# Sheet1.net
KiCad netlist of a schematic drawn in Altium Designer
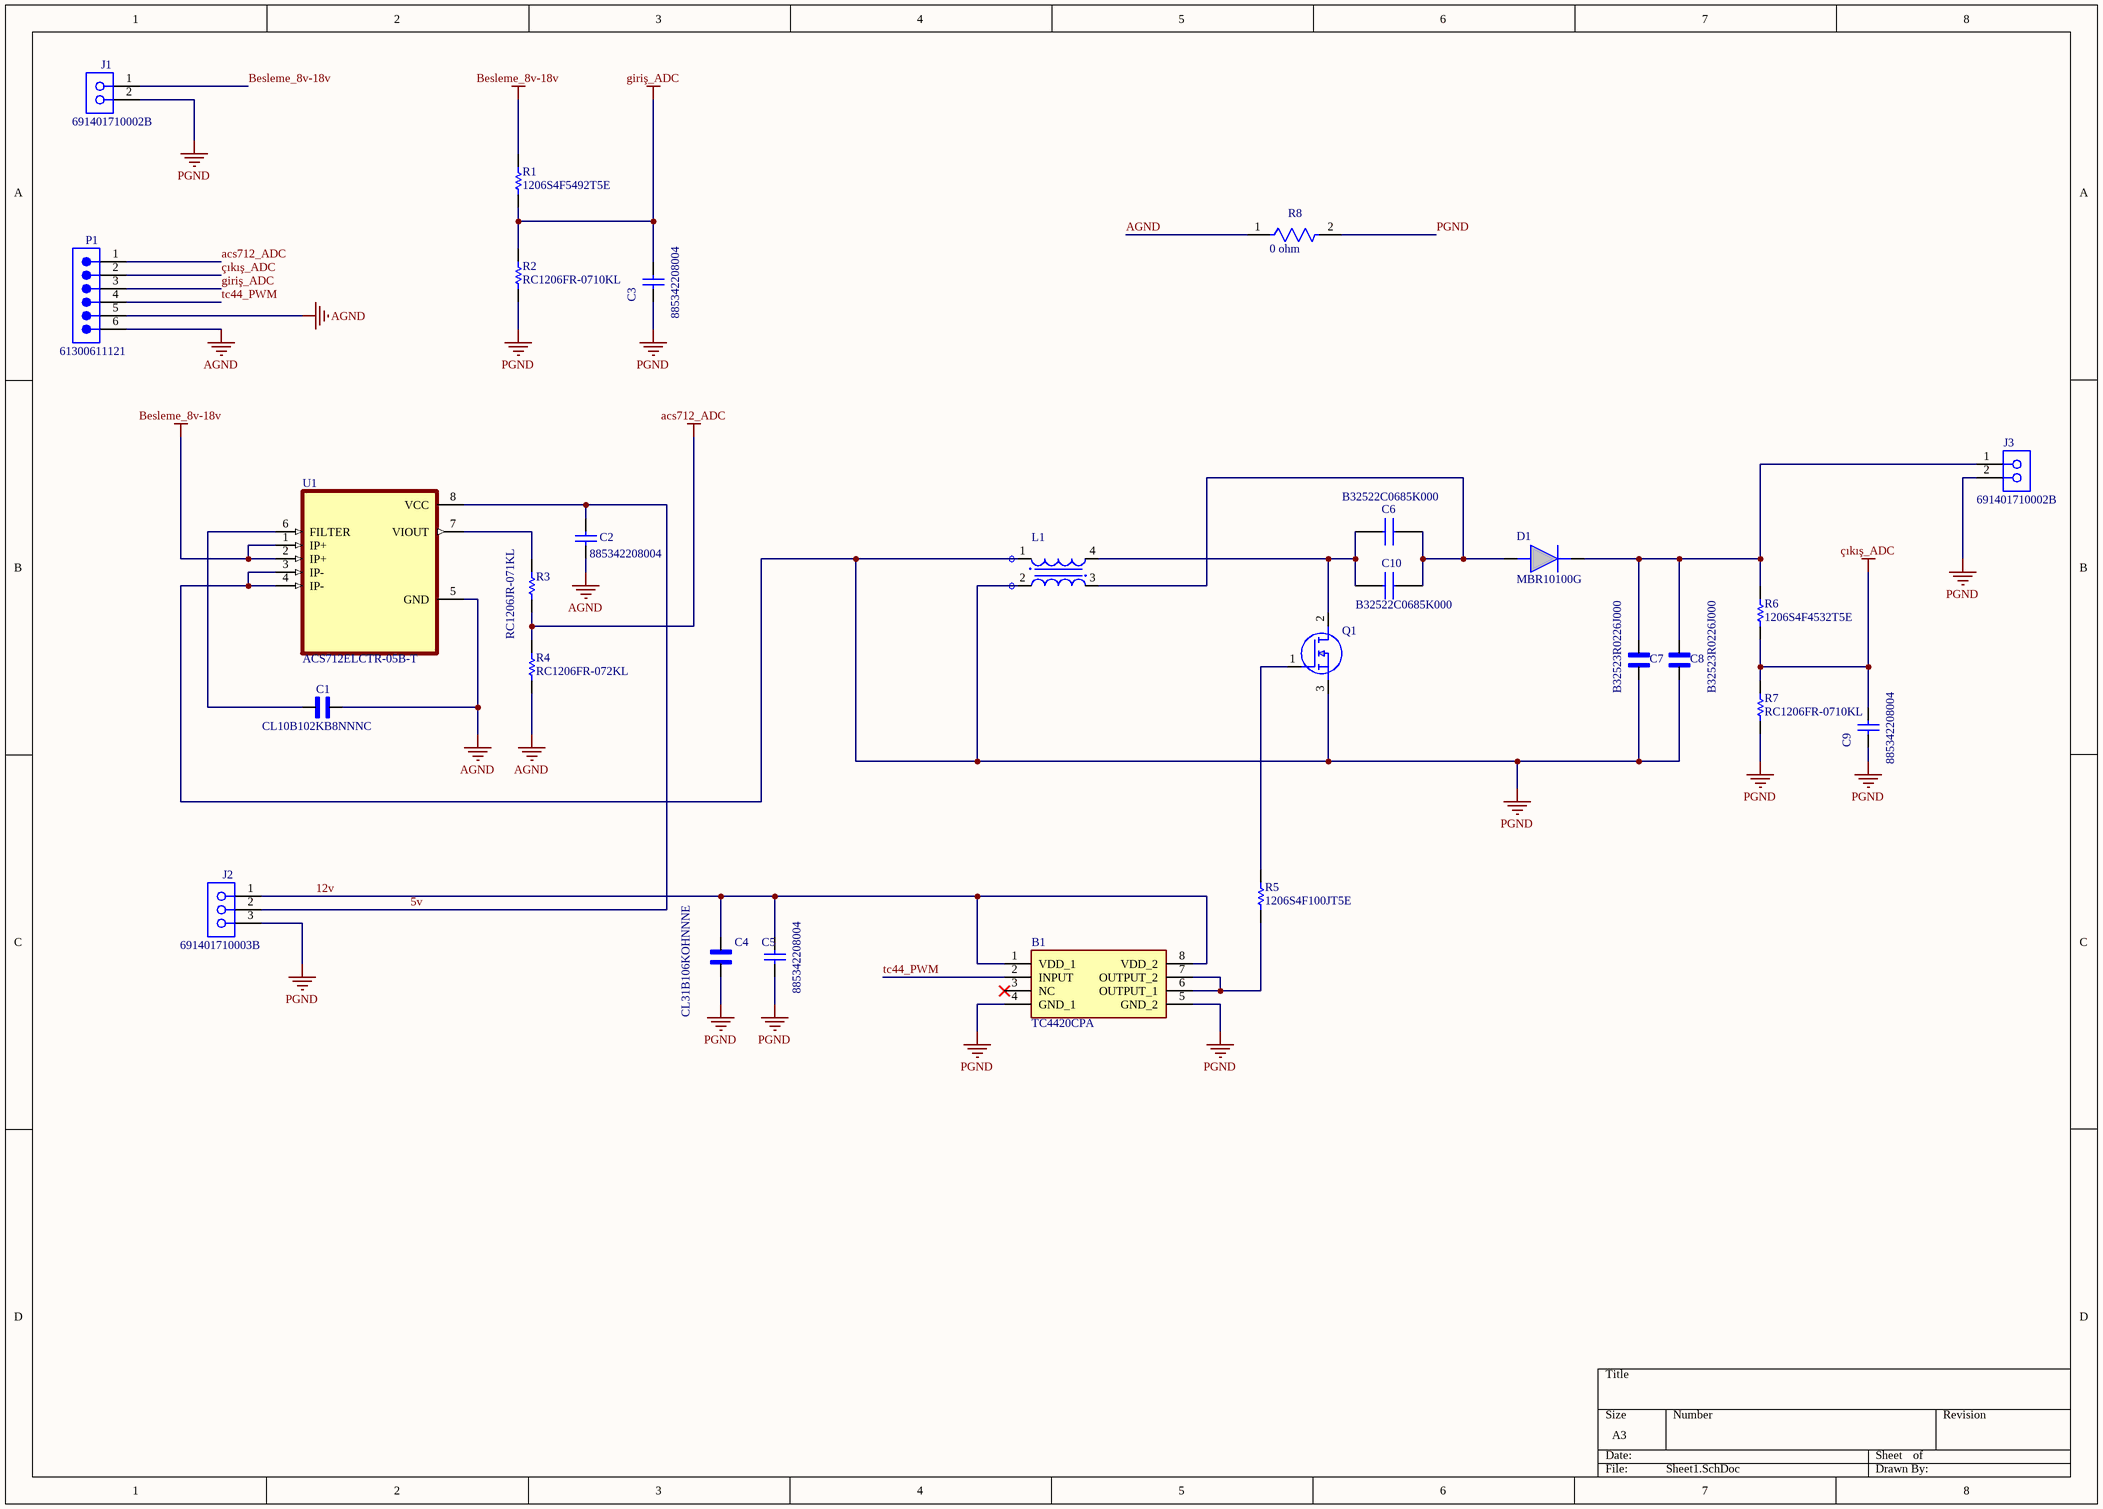
[diagram p0: Sheet1.SchDoc]

(export (version "E")
  (design (tool "Eeschema 10.0.6"))
  (components
    (comp (ref "B1")
      (value "TC4420CPA")
      (footprint "DIP794W56P254L946H432Q8N")
      (description "Microchip TC4420CPA, MOSFET Power Driver 6A, 4.5  18 V, Non-Inverting, 8-Pin PDIP")
      (fields (field (name "MOUSER PART NUMBER") "579-TC4420CPA"))
      (libsource (lib "bitirme_2209_Library2") (part "TC4420CPA"))
    )
    (comp (ref "C1")
      (value "CL10B102KB8NNNC")
      (footprint "CAPC1608X90N")
      (fields (field (name "MF") "{'manufacturer': u'Samsung Electro-Mechanics'}"))
      (libsource (lib "bitirme_2209_Library2") (part "CL10B102KB8NNNC"))
    )
    (comp (ref "C2")
      (value "885342208004")
      (footprint "WCAP-CSMH_1206_H1.6")
      (description "0.1μF ±10% 250V Ceramic Capacitor X7R 1206 (3216 Metric)")
      (libsource (lib "Library2_bitirme_yeni") (part "CMP-03913-89205750-2"))
    )
    (comp (ref "C3")
      (value "885342208004")
      (footprint "WCAP-CSMH_1206_H1.6")
      (description "0.1μF ±10% 250V Ceramic Capacitor X7R 1206 (3216 Metric)")
      (libsource (lib "bitirme_2209_Library2") (part "CMP-03913-89205750-2"))
    )
    (comp (ref "C4")
      (value "CL31B106KOHNNNE")
      (footprint "CAPC3216X180N")
      (description "10 ÂµF Â±10% 16V Ceramic Capacitor X7R 1206 (3216 Metric)")
      (fields (field (name "MF") "Samsung"))
      (libsource (lib "bitirme_2209_Library2") (part "CL31B106KOHNNNE"))
    )
    (comp (ref "C5")
      (value "885342208004")
      (footprint "WCAP-CSMH_1206_H1.6")
      (description "0.1μF ±10% 250V Ceramic Capacitor X7R 1206 (3216 Metric)")
      (libsource (lib "bitirme_2209_Library2") (part "CMP-03913-89205750-2"))
    )
    (comp (ref "C6")
      (value "B32522C0685K000")
      (footprint "B32522C0685K000")
      (description "Metallized Polyester Capacitors (MKT), 6.8uF, 63V DC, 8.5mm(W) x 14.5mm(H) x 18mm(L)")
      (fields (field (name "MOUSER PART NUMBER") "871-B32522C685K"))
      (libsource (lib "bitirme_2209_Library2") (part "B32522C0685K000"))
    )
    (comp (ref "C7")
      (value "B32523R0226J000")
      (footprint "CAPRR2250W80L2650T1200H2200")
      (fields (field (name "MF") "TDK"))
      (libsource (lib "bitirme_2209_Library2") (part "B32523R0226J000"))
    )
    (comp (ref "C8")
      (value "B32523R0226J000")
      (footprint "CAPRR2250W80L2650T1200H2200")
      (fields (field (name "MF") "TDK"))
      (libsource (lib "bitirme_2209_Library2") (part "B32523R0226J000"))
    )
    (comp (ref "C9")
      (value "885342208004")
      (footprint "WCAP-CSMH_1206_H1.6")
      (description "0.1μF ±10% 250V Ceramic Capacitor X7R 1206 (3216 Metric)")
      (libsource (lib "bitirme_2209_Library2") (part "CMP-03913-89205750-2"))
    )
    (comp (ref "C10")
      (value "B32522C0685K000")
      (footprint "B32522C0685K000")
      (description "Metallized Polyester Capacitors (MKT), 6.8uF, 63V DC, 8.5mm(W) x 14.5mm(H) x 18mm(L)")
      (fields (field (name "MOUSER PART NUMBER") "871-B32522C685K"))
      (libsource (lib "bitirme_2209_Library2") (part "B32522C0685K000"))
    )
    (comp (ref "D1")
      (value "MBR10100G")
      (footprint "TO508P997X444X1905-2")
      (fields (field (name "MOUSER PART NUMBER") "863-MBR10100G"))
      (libsource (lib "bitirme_2209_Library2") (part "MBR10100G"))
    )
    (comp (ref "J1")
      (value "691401710002B")
      (footprint "691401710002B")
      (description "Terminal Block, 5.00MM Screwless Horizontal, 2.0MM 2 Wires, 14-24 AWG, 2 Pin")
      (libsource (lib "bitirme_2209_Library2") (part "CMP-1502-03003-3"))
    )
    (comp (ref "J2")
      (value "691401710003B")
      (footprint "691401710003B")
      (description "Terminal Block, 5.00MM Screwless Horizontal, 2.0MM 2 Wires, 14-24 AWG, 3 Pin")
      (libsource (lib "bitirme_2209_Library2") (part "CMP-1502-03004-3"))
    )
    (comp (ref "J3")
      (value "691401710002B")
      (footprint "691401710002B")
      (description "Terminal Block, 5.00MM Screwless Horizontal, 2.0MM 2 Wires, 14-24 AWG, 2 Pin")
      (libsource (lib "bitirme_2209_Library2") (part "CMP-1502-03003-3"))
    )
    (comp (ref "L1")
      (value "WE-CFWI_1312")
      (footprint "caupled ınductor")
      (fields
        (field (name "MF") "{'manufacturer': u'~{W}xfcrth Elektronik'}")
        (field (name "MP") "74485540101")
      )
      (libsource (lib "Library2_bitirme_yeni") (part "WE-CFWI_1312"))
    )
    (comp (ref "P1")
      (value "61300611121")
      (footprint "61300611121")
      (description "THT Vertical Pin Header WR-PHD, Pitch 2.54 mm, Single Row, 6 pins")
      (libsource (lib "bitirme_2209_Library2") (part "CMP-1502-01070-4"))
    )
    (comp (ref "Q1")
      (value "IXTP110N055T2 hortizol")
      (footprint "TO254P1054X470X1955-3")
      (fields
        (field (name "MF") "{'manufacturer': u'Texas Instruments'}")
        (field (name "MP") "LM7805CT/NOPB")
      )
      (libsource (lib "bitirme_2209_Library2") (part "LM7805CT/NOPB"))
    )
    (comp (ref "R1")
      (value "1206S4F5492T5E")
      (footprint "RESC3116X65X40ML10T20")
      (description "Chip Resistor, 10 KOhm, +/- 1%, 0.25 W, -55 to 155 degC, 1206 (3216 Metric), RoHS, Tape and Reel")
      (fields (field (name "TOLERANCE") "1%") (field (name "MANUFACTURER") "Yageo"))
      (libsource (lib "bitirme_2209_Library2") (part "RC1206FR-0710KL"))
    )
    (comp (ref "R2")
      (value "RC1206FR-0710KL")
      (footprint "RESC3116X65X40ML10T20")
      (description "Chip Resistor, 10 KOhm, +/- 1%, 0.25 W, -55 to 155 degC, 1206 (3216 Metric), RoHS, Tape and Reel")
      (fields (field (name "TOLERANCE") "1%") (field (name "MANUFACTURER") "Yageo"))
      (libsource (lib "bitirme_2209_Library2") (part "RC1206FR-0710KL"))
    )
    (comp (ref "R3")
      (value "RC1206JR-071KL")
      (footprint "RESC3116X65X40ML10T20")
      (description "Chip Resistor, 10 KOhm, +/- 1%, 0.25 W, -55 to 155 degC, 1206 (3216 Metric), RoHS, Tape and Reel")
      (fields (field (name "TOLERANCE") "1%") (field (name "MANUFACTURER") "Yageo"))
      (libsource (lib "bitirme_2209_Library2") (part "RC1206FR-0710KL"))
    )
    (comp (ref "R4")
      (value "RC1206FR-072KL")
      (footprint "RESC3116X65X40ML10T20")
      (fields (field (name "MANUFACTURER") "Yageo") (field (name "PART NUMBER") "RC1206FR-101K21L"))
      (libsource (lib "bitirme_2209_Library2") (part "RC1206FR-072KL"))
    )
    (comp (ref "R5")
      (value "1206S4F100JT5E")
      (footprint "RESC3116X65X40ML10T20")
      (description "Chip Resistor, 10 KOhm, +/- 1%, 0.25 W, -55 to 155 degC, 1206 (3216 Metric), RoHS, Tape and Reel")
      (fields (field (name "TOLERANCE") "1%") (field (name "MANUFACTURER") "Yageo"))
      (libsource (lib "bitirme_2209_Library2") (part "RC1206FR-0736KL"))
    )
    (comp (ref "R6")
      (value "1206S4F4532T5E")
      (footprint "RESC3116X65X40ML10T20")
      (description "Chip Resistor, 10 KOhm, +/- 1%, 0.25 W, -55 to 155 degC, 1206 (3216 Metric), RoHS, Tape and Reel")
      (fields (field (name "TOLERANCE") "1%") (field (name "MANUFACTURER") "Yageo"))
      (libsource (lib "bitirme_2209_Library2") (part "RC1206FR-0710KL"))
    )
    (comp (ref "R7")
      (value "RC1206FR-0710KL")
      (footprint "RESC3116X65X40ML10T20")
      (description "Chip Resistor, 10 KOhm, +/- 1%, 0.25 W, -55 to 155 degC, 1206 (3216 Metric), RoHS, Tape and Reel")
      (fields (field (name "TOLERANCE") "1%") (field (name "MANUFACTURER") "Yageo"))
      (libsource (lib "bitirme_2209_Library2") (part "RC1206FR-0710KL"))
    )
    (comp (ref "R8")
      (value "0 ohm")
      (footprint "FP-RT0805-MFG")
      (description "RES SMD 681 OHM 0.1% 1/8W 0805")
      (fields
        (field (name "MANUFACTURER") "Yageo")
        (field (name "MANUFACTURER PART NUMBER") "RT0805BRD07681RL")
      )
      (libsource (lib "bitirme_2209_Library2") (part "0 ohm"))
    )
    (comp (ref "U1")
      (value "ACS712ELCTR-05B-T")
      (footprint "SOIC127P600X175-8N")
      (fields (field (name "MF") "{'manufacturer': u'Allegro MicroSystems'}"))
      (libsource (lib "bitirme_2209_Library2") (part "ACS712ELCTR-05B-T"))
    )
  )
  (nets
    (net (code "1") (name "/5v") (class "Default")
      (node (ref "C2") (pin "2") (pinfunction "2_2") (pintype "passive"))
      (node (ref "J2") (pin "2") (pinfunction "2_2") (pintype "passive"))
      (node (ref "U1") (pin "8") (pinfunction "VCC_8") (pintype "power_in"))
    )
    (net (code "2") (name "/12v") (class "Default")
      (node (ref "B1") (pin "1") (pinfunction "VDD_1_1") (pintype "passive"))
      (node (ref "B1") (pin "8") (pinfunction "VDD_2_8") (pintype "passive"))
      (node (ref "C4") (pin "2") (pinfunction "2_2") (pintype "passive"))
      (node (ref "C5") (pin "2") (pinfunction "2_2") (pintype "passive"))
      (node (ref "J2") (pin "1") (pinfunction "1_1") (pintype "passive"))
    )
    (net (code "3") (name "/tc44_PWM") (class "Default")
      (node (ref "B1") (pin "2") (pinfunction "INPUT_2") (pintype "passive"))
      (node (ref "P1") (pin "4") (pinfunction "4_4") (pintype "passive"))
    )
    (net (code "4") (name "AGND") (class "Default")
      (node (ref "C1") (pin "2") (pinfunction "2_2") (pintype "passive"))
      (node (ref "C2") (pin "1") (pinfunction "1_1") (pintype "passive"))
      (node (ref "P1") (pin "5") (pinfunction "5_5") (pintype "passive"))
      (node (ref "P1") (pin "6") (pinfunction "6_6") (pintype "passive"))
      (node (ref "R4") (pin "1") (pinfunction "1_1") (pintype "passive"))
      (node (ref "R8") (pin "1") (pinfunction "1_1") (pintype "passive"))
      (node (ref "U1") (pin "5") (pinfunction "GND_5") (pintype "power_in"))
    )
    (net (code "5") (name "Besleme_8v-18v") (class "Default")
      (node (ref "J1") (pin "1") (pinfunction "1_1") (pintype "passive"))
      (node (ref "R1") (pin "2") (pinfunction "2_2") (pintype "passive"))
      (node (ref "U1") (pin "1") (pinfunction "IP+_1") (pintype "input"))
      (node (ref "U1") (pin "2") (pinfunction "IP+_2") (pintype "input"))
    )
    (net (code "6") (name "Net-(B1-OUTPUT_1)") (class "Default")
      (node (ref "B1") (pin "6") (pinfunction "OUTPUT_1_6") (pintype "passive"))
      (node (ref "B1") (pin "7") (pinfunction "OUTPUT_2_7") (pintype "passive"))
      (node (ref "R5") (pin "1") (pinfunction "1_1") (pintype "passive"))
    )
    (net (code "7") (name "Net-(D1-A)") (class "Default")
      (node (ref "C10") (pin "2") (pinfunction "2_2") (pintype "passive"))
      (node (ref "C6") (pin "2") (pinfunction "2_2") (pintype "passive"))
      (node (ref "D1") (pin "3") (pinfunction "A_3") (pintype "passive"))
      (node (ref "L1") (pin "3") (pinfunction "3_3") (pintype "passive"))
    )
    (net (code "8") (name "Net-(D1-K)") (class "Default")
      (node (ref "C7") (pin "2") (pinfunction "2_2") (pintype "passive"))
      (node (ref "C8") (pin "2") (pinfunction "2_2") (pintype "passive"))
      (node (ref "D1") (pin "1") (pinfunction "K_1") (pintype "passive"))
      (node (ref "J3") (pin "1") (pinfunction "1_1") (pintype "passive"))
      (node (ref "R6") (pin "2") (pinfunction "2_2") (pintype "passive"))
    )
    (net (code "9") (name "Net-(L1-2)") (class "Default")
      (node (ref "C10") (pin "1") (pinfunction "1_1") (pintype "passive"))
      (node (ref "C6") (pin "1") (pinfunction "1_1") (pintype "passive"))
      (node (ref "L1") (pin "4") (pinfunction "2_4") (pintype "passive"))
      (node (ref "Q1") (pin "2") (pinfunction "D_2") (pintype "passive"))
    )
    (net (code "10") (name "Net-(Q1-G)") (class "Default")
      (node (ref "Q1") (pin "1") (pinfunction "G_1") (pintype "passive"))
      (node (ref "R5") (pin "2") (pinfunction "2_2") (pintype "passive"))
    )
    (net (code "11") (name "Net-(U1-FILTER)") (class "Default")
      (node (ref "C1") (pin "1") (pinfunction "1_1") (pintype "passive"))
      (node (ref "U1") (pin "6") (pinfunction "FILTER_6") (pintype "input"))
    )
    (net (code "12") (name "Net-(U1-VIOUT)") (class "Default")
      (node (ref "R3") (pin "2") (pinfunction "2_2") (pintype "passive"))
      (node (ref "U1") (pin "7") (pinfunction "VIOUT_7") (pintype "output"))
    )
    (net (code "13") (name "PGND") (class "Default")
      (node (ref "B1") (pin "4") (pinfunction "GND_1_4") (pintype "passive"))
      (node (ref "B1") (pin "5") (pinfunction "GND_2_5") (pintype "passive"))
      (node (ref "C3") (pin "1") (pinfunction "1_1") (pintype "passive"))
      (node (ref "C4") (pin "1") (pinfunction "1_1") (pintype "passive"))
      (node (ref "C5") (pin "1") (pinfunction "1_1") (pintype "passive"))
      (node (ref "C7") (pin "1") (pinfunction "1_1") (pintype "passive"))
      (node (ref "C8") (pin "1") (pinfunction "1_1") (pintype "passive"))
      (node (ref "C9") (pin "1") (pinfunction "1_1") (pintype "passive"))
      (node (ref "J1") (pin "2") (pinfunction "2_2") (pintype "passive"))
      (node (ref "J2") (pin "3") (pinfunction "3_3") (pintype "passive"))
      (node (ref "J3") (pin "2") (pinfunction "2_2") (pintype "passive"))
      (node (ref "L1") (pin "1") (pinfunction "1_1") (pintype "passive"))
      (node (ref "L1") (pin "2") (pinfunction "4_2") (pintype "passive"))
      (node (ref "Q1") (pin "3") (pinfunction "S_3") (pintype "passive"))
      (node (ref "R2") (pin "1") (pinfunction "1_1") (pintype "passive"))
      (node (ref "R7") (pin "1") (pinfunction "1_1") (pintype "passive"))
      (node (ref "R8") (pin "2") (pinfunction "2_2") (pintype "passive"))
      (node (ref "U1") (pin "3") (pinfunction "IP-_3") (pintype "input"))
      (node (ref "U1") (pin "4") (pinfunction "IP-_4") (pintype "input"))
    )
    (net (code "14") (name "acs712_ADC") (class "Default")
      (node (ref "P1") (pin "1") (pinfunction "1_1") (pintype "passive"))
      (node (ref "R3") (pin "1") (pinfunction "1_1") (pintype "passive"))
      (node (ref "R4") (pin "2") (pinfunction "2_2") (pintype "passive"))
    )
    (net (code "15") (name "giriş_ADC") (class "Default")
      (node (ref "C3") (pin "2") (pinfunction "2_2") (pintype "passive"))
      (node (ref "P1") (pin "3") (pinfunction "3_3") (pintype "passive"))
      (node (ref "R1") (pin "1") (pinfunction "1_1") (pintype "passive"))
      (node (ref "R2") (pin "2") (pinfunction "2_2") (pintype "passive"))
    )
    (net (code "16") (name "unconnected-(B1-NC-Pad3)") (class "Default")
      (node (ref "B1") (pin "3") (pinfunction "NC_3") (pintype "passive+no_connect"))
    )
    (net (code "17") (name "çıkış_ADC") (class "Default")
      (node (ref "C9") (pin "2") (pinfunction "2_2") (pintype "passive"))
      (node (ref "P1") (pin "2") (pinfunction "2_2") (pintype "passive"))
      (node (ref "R6") (pin "1") (pinfunction "1_1") (pintype "passive"))
      (node (ref "R7") (pin "2") (pinfunction "2_2") (pintype "passive"))
    )
  )
)
